# untitledfix.net
KiCad netlist of a schematic drawn in EAGLE
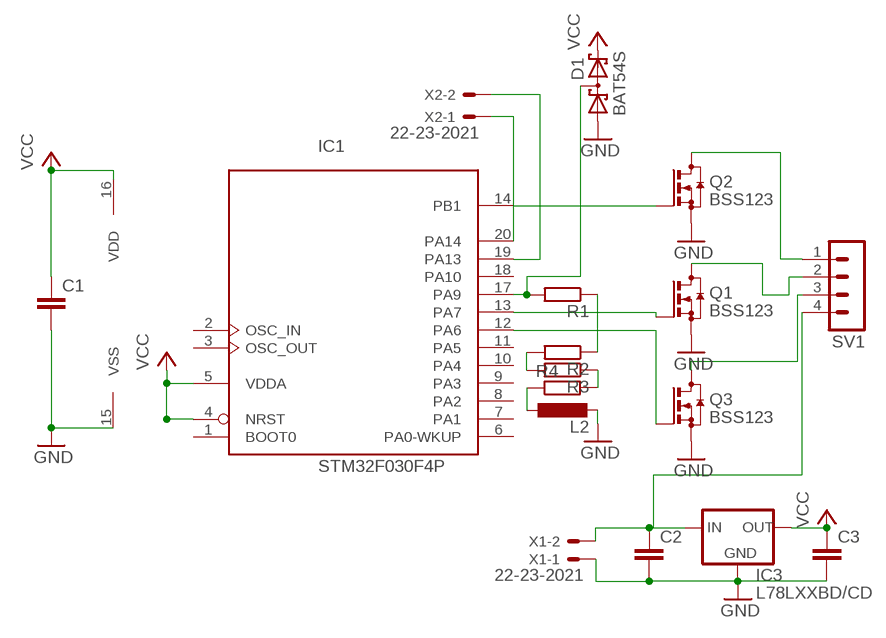
[diagram p0: schematic, sheet 1]

(export (version "E")
  (design (tool "Eeschema 10.0.6"))
  (components
    (comp (ref "C1")
      (value "C-EUC0805K")
      (footprint "eagle-import:C0805K")
      (libsource (lib "eagle-import") (part "C-EUC0805K"))
    )
    (comp (ref "C2")
      (value "C-EUC0805K")
      (footprint "eagle-import:C0805K")
      (libsource (lib "eagle-import") (part "C-EUC0805K"))
    )
    (comp (ref "C3")
      (value "C-EUC0805K")
      (footprint "eagle-import:C0805K")
      (libsource (lib "eagle-import") (part "C-EUC0805K"))
    )
    (comp (ref "D1")
      (value "BAT54S")
      (footprint "eagle-import:SOT23")
      (libsource (lib "eagle-import") (part "BAT54S"))
    )
    (comp (ref "IC1")
      (value "STM32F030F4P")
      (footprint "eagle-import:TSSOP20-I")
      (libsource (lib "eagle-import") (part "STM32F030FP4"))
    )
    (comp (ref "IC3")
      (value "L78LXXBD/CD")
      (footprint "eagle-import:SO08")
      (libsource (lib "eagle-import") (part "L78LXXBD/CD"))
    )
    (comp (ref "L2")
      (value "L-EU0207/5V")
      (footprint "eagle-import:0207_5V")
      (libsource (lib "eagle-import") (part "L-EU0207/5V"))
    )
    (comp (ref "Q1")
      (value "BSS123")
      (footprint "eagle-import:SOT23")
      (libsource (lib "eagle-import") (part "BSS123"))
    )
    (comp (ref "Q2")
      (value "BSS123")
      (footprint "eagle-import:SOT23")
      (libsource (lib "eagle-import") (part "BSS123"))
    )
    (comp (ref "Q3")
      (value "BSS123")
      (footprint "eagle-import:SOT23")
      (libsource (lib "eagle-import") (part "BSS123"))
    )
    (comp (ref "R1")
      (value "R-EU_M0805")
      (footprint "eagle-import:M0805")
      (libsource (lib "eagle-import") (part "R-EU_M0805"))
    )
    (comp (ref "R2")
      (value "R-EU_M0805")
      (footprint "eagle-import:M0805")
      (libsource (lib "eagle-import") (part "R-EU_M0805"))
    )
    (comp (ref "R3")
      (value "R-EU_M0805")
      (footprint "eagle-import:M0805")
      (libsource (lib "eagle-import") (part "R-EU_M0805"))
    )
    (comp (ref "R4")
      (value "R-EU_M0805")
      (footprint "eagle-import:M0805")
      (libsource (lib "eagle-import") (part "R-EU_M0805"))
    )
    (comp (ref "SV1")
      (value "MA04-1")
      (footprint "eagle-import:MA04-1")
      (libsource (lib "eagle-import") (part "MA04-1"))
    )
    (comp (ref "X1")
      (value "22-23-2021")
      (footprint "eagle-import:22-23-2021")
      (fields (field (name "MF") "MOLEX"))
      (libsource (lib "eagle-import") (part "22-23-2021"))
    )
    (comp (ref "X2")
      (value "22-23-2021")
      (footprint "eagle-import:22-23-2021")
      (fields (field (name "MF") "MOLEX"))
      (libsource (lib "eagle-import") (part "22-23-2021"))
    )
  )
  (nets
    (net (code "1") (name "GND") (class "Default")
      (node (ref "C1") (pin "2") (pinfunction "2_2") (pintype "passive"))
      (node (ref "C2") (pin "2") (pinfunction "2_2") (pintype "passive"))
      (node (ref "C3") (pin "2") (pinfunction "2_2") (pintype "passive"))
      (node (ref "D1") (pin "1") (pinfunction "A1_1") (pintype "passive"))
      (node (ref "IC1") (pin "15") (pinfunction "VSS_15") (pintype "power_in"))
      (node (ref "IC3") (pin "2") (pinfunction "GND1_2") (pintype "input"))
      (node (ref "IC3") (pin "3") (pinfunction "GND3_3") (pintype "input"))
      (node (ref "IC3") (pin "6") (pinfunction "GND4_6") (pintype "input"))
      (node (ref "IC3") (pin "7") (pinfunction "GND2_7") (pintype "input"))
      (node (ref "L2") (pin "2") (pinfunction "2_2") (pintype "passive"))
      (node (ref "Q1") (pin "2") (pinfunction "S_2") (pintype "passive"))
      (node (ref "Q2") (pin "2") (pinfunction "S_2") (pintype "passive"))
      (node (ref "Q3") (pin "2") (pinfunction "S_2") (pintype "passive"))
      (node (ref "X1") (pin "1") (pinfunction "S_1") (pintype "passive"))
    )
    (net (code "2") (name "Net-(D1-C1A2)") (class "Default")
      (node (ref "D1") (pin "3") (pinfunction "C1A2_3") (pintype "passive"))
      (node (ref "IC1") (pin "17") (pinfunction "PA9_17") (pintype "bidirectional"))
      (node (ref "R1") (pin "2") (pinfunction "2_2") (pintype "passive"))
    )
    (net (code "3") (name "Net-(IC1A-PA6)") (class "Default")
      (node (ref "IC1") (pin "12") (pinfunction "PA6_12") (pintype "bidirectional"))
      (node (ref "Q3") (pin "1") (pinfunction "G_1") (pintype "passive"))
    )
    (net (code "4") (name "Net-(IC1A-PA7)") (class "Default")
      (node (ref "IC1") (pin "13") (pinfunction "PA7_13") (pintype "bidirectional"))
      (node (ref "Q1") (pin "1") (pinfunction "G_1") (pintype "passive"))
    )
    (net (code "5") (name "Net-(IC1A-PA13)") (class "Default")
      (node (ref "IC1") (pin "19") (pinfunction "PA13_19") (pintype "bidirectional"))
      (node (ref "X2") (pin "2") (pinfunction "S_2") (pintype "passive"))
    )
    (net (code "6") (name "Net-(IC1A-PA14)") (class "Default")
      (node (ref "IC1") (pin "20") (pinfunction "PA14_20") (pintype "bidirectional"))
      (node (ref "X2") (pin "1") (pinfunction "S_1") (pintype "passive"))
    )
    (net (code "7") (name "Net-(IC1A-PB1)") (class "Default")
      (node (ref "IC1") (pin "14") (pinfunction "PB1_14") (pintype "bidirectional"))
      (node (ref "Q2") (pin "1") (pinfunction "G_1") (pintype "passive"))
    )
    (net (code "8") (name "Net-(IC3-IN)") (class "Default")
      (node (ref "C2") (pin "1") (pinfunction "1_1") (pintype "passive"))
      (node (ref "IC3") (pin "8") (pinfunction "IN_8") (pintype "input"))
      (node (ref "SV1") (pin "4") (pinfunction "4_4") (pintype "passive"))
      (node (ref "X1") (pin "2") (pinfunction "S_2") (pintype "passive"))
    )
    (net (code "9") (name "Net-(L2-Pad1)") (class "Default")
      (node (ref "L2") (pin "1") (pinfunction "1_1") (pintype "passive"))
      (node (ref "R4") (pin "1") (pinfunction "1_1") (pintype "passive"))
    )
    (net (code "10") (name "Net-(Q1-D)") (class "Default")
      (node (ref "Q1") (pin "3") (pinfunction "D_3") (pintype "passive"))
      (node (ref "SV1") (pin "2") (pinfunction "2_2") (pintype "passive"))
    )
    (net (code "11") (name "Net-(Q2-D)") (class "Default")
      (node (ref "Q2") (pin "3") (pinfunction "D_3") (pintype "passive"))
      (node (ref "SV1") (pin "1") (pinfunction "1_1") (pintype "passive"))
    )
    (net (code "12") (name "Net-(Q3-D)") (class "Default")
      (node (ref "Q3") (pin "3") (pinfunction "D_3") (pintype "passive"))
      (node (ref "SV1") (pin "3") (pinfunction "3_3") (pintype "passive"))
    )
    (net (code "13") (name "Net-(R1-Pad1)") (class "Default")
      (node (ref "R1") (pin "1") (pinfunction "1_1") (pintype "passive"))
      (node (ref "R2") (pin "1") (pinfunction "1_1") (pintype "passive"))
    )
    (net (code "14") (name "Net-(R2-Pad2)") (class "Default")
      (node (ref "R2") (pin "2") (pinfunction "2_2") (pintype "passive"))
      (node (ref "R3") (pin "2") (pinfunction "2_2") (pintype "passive"))
    )
    (net (code "15") (name "Net-(R3-Pad1)") (class "Default")
      (node (ref "R3") (pin "1") (pinfunction "1_1") (pintype "passive"))
      (node (ref "R4") (pin "2") (pinfunction "2_2") (pintype "passive"))
    )
    (net (code "16") (name "VCC") (class "Default")
      (node (ref "C1") (pin "1") (pinfunction "1_1") (pintype "passive"))
      (node (ref "C3") (pin "1") (pinfunction "1_1") (pintype "passive"))
      (node (ref "D1") (pin "2") (pinfunction "C2_2") (pintype "passive"))
      (node (ref "IC1") (pin "16") (pinfunction "VDD_16") (pintype "power_in"))
      (node (ref "IC1") (pin "4") (pinfunction "NRST_4") (pintype "bidirectional"))
      (node (ref "IC1") (pin "5") (pinfunction "VDDA_5") (pintype "power_in"))
      (node (ref "IC3") (pin "1") (pinfunction "OUT_1") (pintype "passive"))
    )
    (net (code "17") (name "unconnected-(IC1A-BOOT0-Pad1)") (class "Default")
      (node (ref "IC1") (pin "1") (pinfunction "BOOT0_1") (pintype "input"))
    )
    (net (code "18") (name "unconnected-(IC1A-OSC_IN-Pad2)") (class "Default")
      (node (ref "IC1") (pin "2") (pinfunction "OSC_IN_2") (pintype "bidirectional"))
    )
    (net (code "19") (name "unconnected-(IC1A-OSC_OUT-Pad3)") (class "Default")
      (node (ref "IC1") (pin "3") (pinfunction "OSC_OUT_3") (pintype "bidirectional"))
    )
    (net (code "20") (name "unconnected-(IC1A-PA0-WKUP-Pad6)") (class "Default")
      (node (ref "IC1") (pin "6") (pinfunction "PA0-WKUP_6") (pintype "bidirectional"))
    )
    (net (code "21") (name "unconnected-(IC1A-PA1-Pad7)") (class "Default")
      (node (ref "IC1") (pin "7") (pinfunction "PA1_7") (pintype "bidirectional"))
    )
    (net (code "22") (name "unconnected-(IC1A-PA2-Pad8)") (class "Default")
      (node (ref "IC1") (pin "8") (pinfunction "PA2_8") (pintype "bidirectional"))
    )
    (net (code "23") (name "unconnected-(IC1A-PA3-Pad9)") (class "Default")
      (node (ref "IC1") (pin "9") (pinfunction "PA3_9") (pintype "bidirectional"))
    )
    (net (code "24") (name "unconnected-(IC1A-PA4-Pad10)") (class "Default")
      (node (ref "IC1") (pin "10") (pinfunction "PA4_10") (pintype "bidirectional"))
    )
    (net (code "25") (name "unconnected-(IC1A-PA5-Pad11)") (class "Default")
      (node (ref "IC1") (pin "11") (pinfunction "PA5_11") (pintype "bidirectional"))
    )
    (net (code "26") (name "unconnected-(IC1A-PA10-Pad18)") (class "Default")
      (node (ref "IC1") (pin "18") (pinfunction "PA10_18") (pintype "bidirectional"))
    )
  )
)
